# NAVIGATION_-_SERVO.net
KiCad netlist of a schematic drawn in Altium Designer
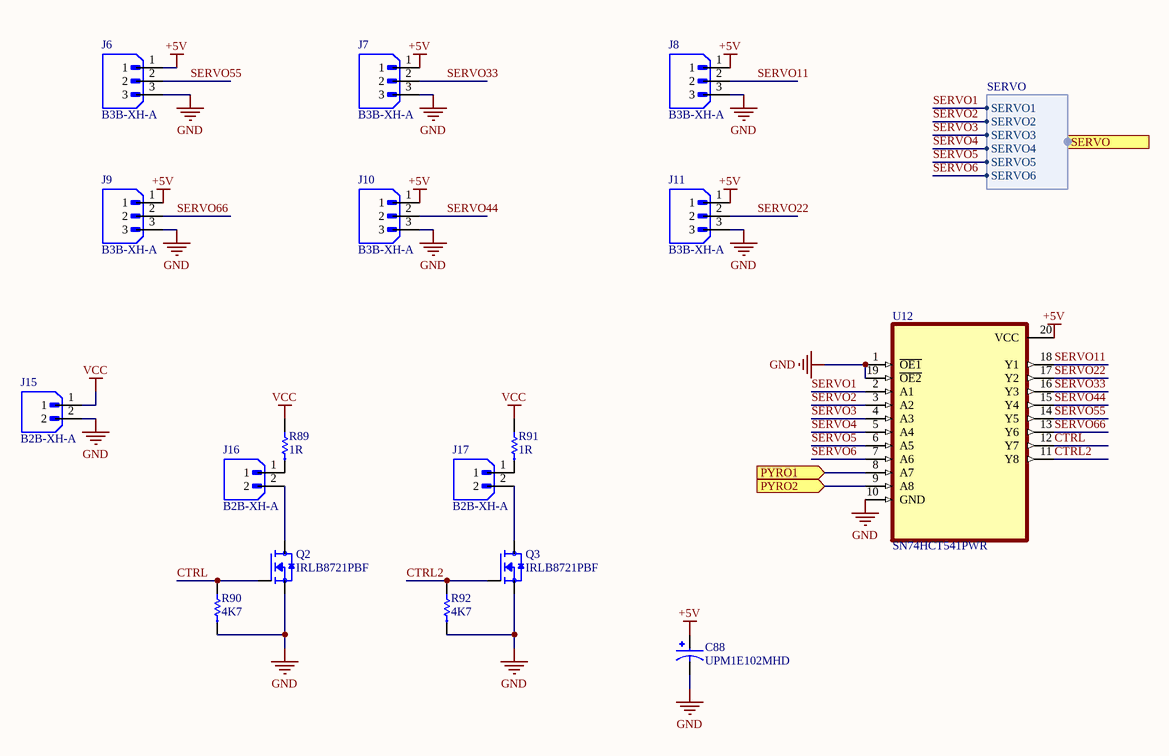
[diagram p0: NAVIGATION - SERVO.SchDoc]

(export (version "E")
  (design (tool "Eeschema 10.0.6"))
  (components
    (comp (ref "C88")
      (value "UPM1E102MHD")
      (footprint "CAPPRD500W80D1250H2700")
      (description "Capacitor Aluminum Electrolytic Cap1000uF 25V 20% Radial 12.5X25 LS 5mm ¦ Nichicon UPM1E102MHD")
      (fields (field (name "MF") "Nichicon"))
      (libsource (lib "UPM1E102MHD") (part "UPM1E102MHD"))
    )
    (comp (ref "J6")
      (value "B3B-XH-A")
      (footprint "JST_B3B-XH-A")
      (description "Connector Header Through Hole 3 position 0.098 (2.50mm)")
      (fields (field (name "MF") "JST Sales"))
      (libsource (lib "B3B-XH-A") (part "B3B-XH-A"))
    )
    (comp (ref "J7")
      (value "B3B-XH-A")
      (footprint "JST_B3B-XH-A")
      (description "Connector Header Through Hole 3 position 0.098 (2.50mm)")
      (fields (field (name "MF") "JST Sales"))
      (libsource (lib "B3B-XH-A") (part "B3B-XH-A"))
    )
    (comp (ref "J8")
      (value "B3B-XH-A")
      (footprint "JST_B3B-XH-A")
      (description "Connector Header Through Hole 3 position 0.098 (2.50mm)")
      (fields (field (name "MF") "JST Sales"))
      (libsource (lib "B3B-XH-A") (part "B3B-XH-A"))
    )
    (comp (ref "J9")
      (value "B3B-XH-A")
      (footprint "JST_B3B-XH-A")
      (description "Connector Header Through Hole 3 position 0.098 (2.50mm)")
      (fields (field (name "MF") "JST Sales"))
      (libsource (lib "B3B-XH-A") (part "B3B-XH-A"))
    )
    (comp (ref "J10")
      (value "B3B-XH-A")
      (footprint "JST_B3B-XH-A")
      (description "Connector Header Through Hole 3 position 0.098 (2.50mm)")
      (fields (field (name "MF") "JST Sales"))
      (libsource (lib "B3B-XH-A") (part "B3B-XH-A"))
    )
    (comp (ref "J11")
      (value "B3B-XH-A")
      (footprint "JST_B3B-XH-A")
      (description "Connector Header Through Hole 3 position 0.098 (2.50mm)")
      (fields (field (name "MF") "JST Sales"))
      (libsource (lib "B3B-XH-A") (part "B3B-XH-A"))
    )
    (comp (ref "J15")
      (value "B2B-XH-A")
      (footprint "JST_B2B-XH-A")
      (fields (field (name "MF") "{'manufacturer': u'JST Sales America Inc.'}"))
      (libsource (lib "B2B-XH-A") (part "B2B-XH-A"))
    )
    (comp (ref "J16")
      (value "B2B-XH-A")
      (footprint "JST_B2B-XH-A")
      (fields (field (name "MF") "{'manufacturer': u'JST Sales America Inc.'}"))
      (libsource (lib "B2B-XH-A") (part "B2B-XH-A"))
    )
    (comp (ref "J17")
      (value "B2B-XH-A")
      (footprint "JST_B2B-XH-A")
      (fields (field (name "MF") "{'manufacturer': u'JST Sales America Inc.'}"))
      (libsource (lib "B2B-XH-A") (part "B2B-XH-A"))
    )
    (comp (ref "Q2")
      (value "IRLB8721PBF")
      (footprint "TO254P1067X483X2057-3")
      (description "IRLB8721PBF N-channel MOSFET Transistor, 62 A, 30 V, 3-Pin TO-220AB ¦ Infineon IRLB8721PBF")
      (fields (field (name "MF") "Infineon Technologies"))
      (libsource (lib "IRLB8721PBF") (part "IRLB8721PBF"))
    )
    (comp (ref "Q3")
      (value "IRLB8721PBF")
      (footprint "TO254P1067X483X2057-3")
      (description "IRLB8721PBF N-channel MOSFET Transistor, 62 A, 30 V, 3-Pin TO-220AB ¦ Infineon IRLB8721PBF")
      (fields (field (name "MF") "Infineon Technologies"))
      (libsource (lib "IRLB8721PBF") (part "IRLB8721PBF"))
    )
    (comp (ref "R89")
      (value "1R")
      (footprint "RES-CHP0402-0.35H")
      (description "RES CHP 0R 1% 1/16W 0402 SMD")
      (libsource (lib "2502-GMQLITE-MAIN") (part "RESCHP0001 0R 1% 0402 SMD"))
    )
    (comp (ref "R90")
      (value "4K7")
      (footprint "RES-CHP0402-0.35H")
      (description "RES CHP 0R 1% 1/16W 0402 SMD")
      (libsource (lib "2502-GMQLITE-MAIN") (part "RESCHP0001 0R 1% 0402 SMD"))
    )
    (comp (ref "R91")
      (value "1R")
      (footprint "RES-CHP0402-0.35H")
      (description "RES CHP 0R 1% 1/16W 0402 SMD")
      (libsource (lib "2502-GMQLITE-MAIN") (part "RESCHP0001 0R 1% 0402 SMD"))
    )
    (comp (ref "R92")
      (value "4K7")
      (footprint "RES-CHP0402-0.35H")
      (description "RES CHP 0R 1% 1/16W 0402 SMD")
      (libsource (lib "2502-GMQLITE-MAIN") (part "RESCHP0001 0R 1% 0402 SMD"))
    )
    (comp (ref "U12")
      (value "SN74HCT541PWR")
      (footprint "SOP65P640X120-20N")
      (libsource (lib "SN74HCT541PWR") (part "SN74HCT541PWR"))
    )
  )
  (nets
    (net (code "2") (name "+5V") (class "Default")
      (node (ref "C88") (pin "P") (pinfunction "P_P") (pintype "passive"))
      (node (ref "J10") (pin "1") (pinfunction "1_1") (pintype "passive"))
      (node (ref "J11") (pin "1") (pinfunction "1_1") (pintype "passive"))
      (node (ref "J6") (pin "1") (pinfunction "1_1") (pintype "passive"))
      (node (ref "J7") (pin "1") (pinfunction "1_1") (pintype "passive"))
      (node (ref "J8") (pin "1") (pinfunction "1_1") (pintype "passive"))
      (node (ref "J9") (pin "1") (pinfunction "1_1") (pintype "passive"))
      (node (ref "U12") (pin "20") (pinfunction "VCC_20") (pintype "power_in"))
    )
    (net (code "3") (name "/CTRL") (class "Default")
      (node (ref "Q2") (pin "1") (pinfunction "G_1") (pintype "passive"))
      (node (ref "R90") (pin "2") (pinfunction "2_2") (pintype "passive"))
      (node (ref "U12") (pin "12") (pinfunction "Y7_12") (pintype "output"))
    )
    (net (code "4") (name "/CTRL2") (class "Default")
      (node (ref "Q3") (pin "1") (pinfunction "G_1") (pintype "passive"))
      (node (ref "R92") (pin "2") (pinfunction "2_2") (pintype "passive"))
      (node (ref "U12") (pin "11") (pinfunction "Y8_11") (pintype "output"))
    )
    (net (code "5") (name "/PYRO1") (class "Default")
      (node (ref "U12") (pin "8") (pinfunction "A7_8") (pintype "input"))
    )
    (net (code "6") (name "/PYRO2") (class "Default")
      (node (ref "U12") (pin "9") (pinfunction "A8_9") (pintype "input"))
    )
    (net (code "7") (name "/SERVO1") (class "Default")
      (node (ref "U12") (pin "2") (pinfunction "A1_2") (pintype "input"))
    )
    (net (code "8") (name "/SERVO2") (class "Default")
      (node (ref "U12") (pin "3") (pinfunction "A2_3") (pintype "input"))
    )
    (net (code "9") (name "/SERVO3") (class "Default")
      (node (ref "U12") (pin "4") (pinfunction "A3_4") (pintype "input"))
    )
    (net (code "10") (name "/SERVO4") (class "Default")
      (node (ref "U12") (pin "5") (pinfunction "A4_5") (pintype "input"))
    )
    (net (code "11") (name "/SERVO5") (class "Default")
      (node (ref "U12") (pin "6") (pinfunction "A5_6") (pintype "input"))
    )
    (net (code "12") (name "/SERVO6") (class "Default")
      (node (ref "U12") (pin "7") (pinfunction "A6_7") (pintype "input"))
    )
    (net (code "13") (name "/SERVO11") (class "Default")
      (node (ref "J8") (pin "2") (pinfunction "2_2") (pintype "passive"))
      (node (ref "U12") (pin "18") (pinfunction "Y1_18") (pintype "output"))
    )
    (net (code "14") (name "/SERVO22") (class "Default")
      (node (ref "J11") (pin "2") (pinfunction "2_2") (pintype "passive"))
      (node (ref "U12") (pin "17") (pinfunction "Y2_17") (pintype "output"))
    )
    (net (code "15") (name "/SERVO33") (class "Default")
      (node (ref "J7") (pin "2") (pinfunction "2_2") (pintype "passive"))
      (node (ref "U12") (pin "16") (pinfunction "Y3_16") (pintype "output"))
    )
    (net (code "16") (name "/SERVO44") (class "Default")
      (node (ref "J10") (pin "2") (pinfunction "2_2") (pintype "passive"))
      (node (ref "U12") (pin "15") (pinfunction "Y4_15") (pintype "output"))
    )
    (net (code "17") (name "/SERVO55") (class "Default")
      (node (ref "J6") (pin "2") (pinfunction "2_2") (pintype "passive"))
      (node (ref "U12") (pin "14") (pinfunction "Y5_14") (pintype "output"))
    )
    (net (code "18") (name "/SERVO66") (class "Default")
      (node (ref "J9") (pin "2") (pinfunction "2_2") (pintype "passive"))
      (node (ref "U12") (pin "13") (pinfunction "Y6_13") (pintype "output"))
    )
    (net (code "20") (name "GND") (class "Default")
      (node (ref "C88") (pin "N") (pinfunction "N_N") (pintype "passive"))
      (node (ref "J10") (pin "3") (pinfunction "3_3") (pintype "passive"))
      (node (ref "J11") (pin "3") (pinfunction "3_3") (pintype "passive"))
      (node (ref "J15") (pin "2") (pinfunction "2_2") (pintype "passive"))
      (node (ref "J6") (pin "3") (pinfunction "3_3") (pintype "passive"))
      (node (ref "J7") (pin "3") (pinfunction "3_3") (pintype "passive"))
      (node (ref "J8") (pin "3") (pinfunction "3_3") (pintype "passive"))
      (node (ref "J9") (pin "3") (pinfunction "3_3") (pintype "passive"))
      (node (ref "Q2") (pin "3") (pinfunction "S_3") (pintype "passive"))
      (node (ref "Q3") (pin "3") (pinfunction "S_3") (pintype "passive"))
      (node (ref "R90") (pin "1") (pinfunction "1_1") (pintype "passive"))
      (node (ref "R92") (pin "1") (pinfunction "1_1") (pintype "passive"))
      (node (ref "U12") (pin "1") (pinfunction "~{OE1}_1") (pintype "input"))
      (node (ref "U12") (pin "10") (pinfunction "GND_10") (pintype "input"))
      (node (ref "U12") (pin "19") (pinfunction "~{OE2}_19") (pintype "input"))
    )
    (net (code "21") (name "Net-(J16-Pad1)") (class "Default")
      (node (ref "J16") (pin "1") (pinfunction "1_1") (pintype "passive"))
      (node (ref "R89") (pin "1") (pinfunction "1_1") (pintype "passive"))
    )
    (net (code "22") (name "Net-(J17-Pad1)") (class "Default")
      (node (ref "J17") (pin "1") (pinfunction "1_1") (pintype "passive"))
      (node (ref "R91") (pin "1") (pinfunction "1_1") (pintype "passive"))
    )
    (net (code "23") (name "Net-(Q2-D)") (class "Default")
      (node (ref "J16") (pin "2") (pinfunction "2_2") (pintype "passive"))
      (node (ref "Q2") (pin "2") (pinfunction "D_2") (pintype "passive"))
    )
    (net (code "24") (name "Net-(Q3-D)") (class "Default")
      (node (ref "J17") (pin "2") (pinfunction "2_2") (pintype "passive"))
      (node (ref "Q3") (pin "2") (pinfunction "D_2") (pintype "passive"))
    )
    (net (code "25") (name "VCC") (class "Default")
      (node (ref "J15") (pin "1") (pinfunction "1_1") (pintype "passive"))
      (node (ref "R89") (pin "2") (pinfunction "2_2") (pintype "passive"))
      (node (ref "R91") (pin "2") (pinfunction "2_2") (pintype "passive"))
    )
  )
)
